# LMR514205V.net
KiCad netlist of a schematic drawn in Altium Designer
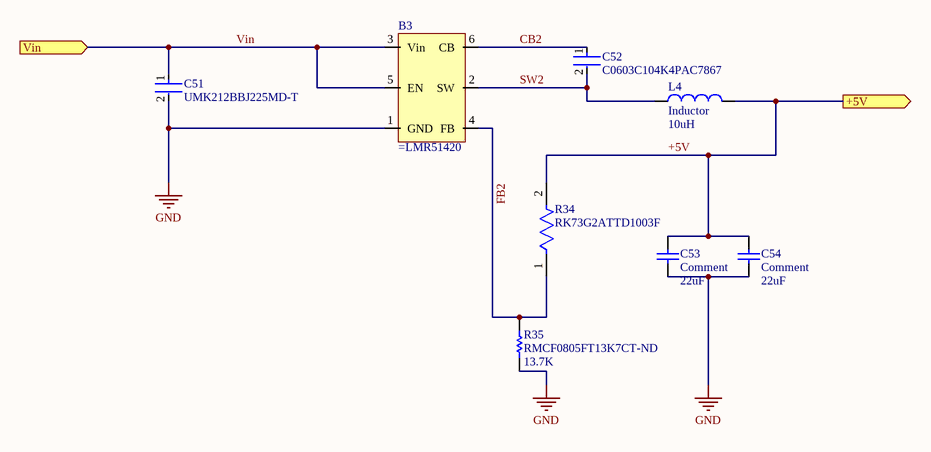
[diagram p0: LMR514205V.SchDoc]

(export (version "E")
  (design (tool "Eeschema 10.0.6"))
  (components
    (comp (ref "B3") (value "~") (footprint "LMR51420IC") (libsource (lib "LMR51420") (part "Component_1")))
    (comp (ref "C51")
      (value "UMK212BBJ225MD-T")
      (footprint "FP-0805-L_2_0_0_2-W_1_25-IPC_A")
      (description "Multilayer Ceramic Capacitor 2.2uF 50V X5R 20% SMD 0803 T/R")
      (fields (field (name "TOLERANCE") "20%"))
      (libsource (lib "Altium Content Vault") (part "02cd4be3c70576c341d710602a673aa"))
    )
    (comp (ref "C52")
      (value "C0603C104K4PAC7867")
      (footprint "CAP CER 0.1UF 16V X7R 0603")
      (description "CAP CER 0.1UF 16V X5R 0603")
      (fields
        (field (name "OCTOPART") "https://octopart.com/c0603c104k4pactu-kemet-12592163")
        (field (name "MANUFACTURER") "KEMET")
      )
      (libsource (lib "Miscellaneous Devices") (part "b4654b650e69147ec39a6b967a45e02"))
    )
    (comp (ref "C53")
      (value "Comment")
      (footprint "Cap22uF_C1206C226M4PAC7800")
      (description "Capacitor")
      (fields (field (name "ALTIUM_VALUE") "22uF") (field (name "PUBLISHER") "Altium Limited"))
      (libsource (lib "Miscellaneous Devices") (part "Cap"))
    )
    (comp (ref "C54")
      (value "Comment")
      (footprint "Cap22uF_C1206C226M4PAC7800")
      (description "Capacitor")
      (fields (field (name "ALTIUM_VALUE") "22uF") (field (name "PUBLISHER") "Altium Limited"))
      (libsource (lib "Miscellaneous Devices") (part "Cap"))
    )
    (comp (ref "L4")
      (value "Inductor")
      (footprint "MSS1246H-103MED 10uH")
      (fields (field (name "ALTIUM_VALUE") "10uH") (field (name "PUBLISHER") "Altium Limited"))
      (libsource (lib "Miscellaneous Devices") (part "Inductor"))
    )
    (comp (ref "R34")
      (value "RK73G2ATTD1003F")
      (footprint "FP-RK73G2A-IPC_A")
      (description "100kΩ ±1% 0.125W Chip Resistor 0805 Thick Film AEC-Q200 Qualified")
      (fields (field (name "TOLERANCE") "1%"))
      (libsource (lib "Altium Content Vault") (part "1029c3af85768c4190bb7ad29bc67b5"))
    )
    (comp (ref "R35")
      (value "RMCF0805FT13K7CT-ND")
      (footprint "RMCF0805FT13K7_13.7k")
      (description "Resistor")
      (fields (field (name "ALTIUM_VALUE") "13.7K") (field (name "PUBLISHER") "Altium Limited"))
      (libsource (lib "Miscellaneous Devices") (part "Res1"))
    )
  )
  (nets
    (net (code "1") (name "/+5V") (class "Default")
      (node (ref "C53") (pin "2") (pinfunction "2_2") (pintype "passive"))
      (node (ref "C54") (pin "2") (pinfunction "2_2") (pintype "passive"))
      (node (ref "L4") (pin "2") (pinfunction "2_2") (pintype "passive"))
      (node (ref "R34") (pin "2") (pinfunction "2_2") (pintype "passive"))
    )
    (net (code "2") (name "/CB2") (class "Default")
      (node (ref "B3") (pin "6") (pinfunction "CB_6") (pintype "passive"))
      (node (ref "C52") (pin "1") (pinfunction "1_1") (pintype "passive"))
    )
    (net (code "3") (name "/FB2") (class "Default")
      (node (ref "B3") (pin "4") (pinfunction "FB_4") (pintype "passive"))
      (node (ref "R34") (pin "1") (pinfunction "1_1") (pintype "passive"))
      (node (ref "R35") (pin "2") (pinfunction "2_2") (pintype "passive"))
    )
    (net (code "4") (name "/SW2") (class "Default")
      (node (ref "B3") (pin "2") (pinfunction "SW_2") (pintype "passive"))
      (node (ref "C52") (pin "2") (pinfunction "2_2") (pintype "passive"))
      (node (ref "L4") (pin "1") (pinfunction "1_1") (pintype "passive"))
    )
    (net (code "5") (name "/Vin") (class "Default")
      (node (ref "B3") (pin "3") (pinfunction "Vin_3") (pintype "passive"))
      (node (ref "B3") (pin "5") (pinfunction "EN_5") (pintype "passive"))
      (node (ref "C51") (pin "1") (pinfunction "1_1") (pintype "passive"))
    )
    (net (code "6") (name "GND") (class "Default")
      (node (ref "B3") (pin "1") (pinfunction "GND_1") (pintype "passive"))
      (node (ref "C51") (pin "2") (pinfunction "2_2") (pintype "passive"))
      (node (ref "C53") (pin "1") (pinfunction "1_1") (pintype "passive"))
      (node (ref "C54") (pin "1") (pinfunction "1_1") (pintype "passive"))
      (node (ref "R35") (pin "1") (pinfunction "1_1") (pintype "passive"))
    )
  )
)
